# MixerHF.net
KiCad netlist of a schematic drawn in Altium Designer
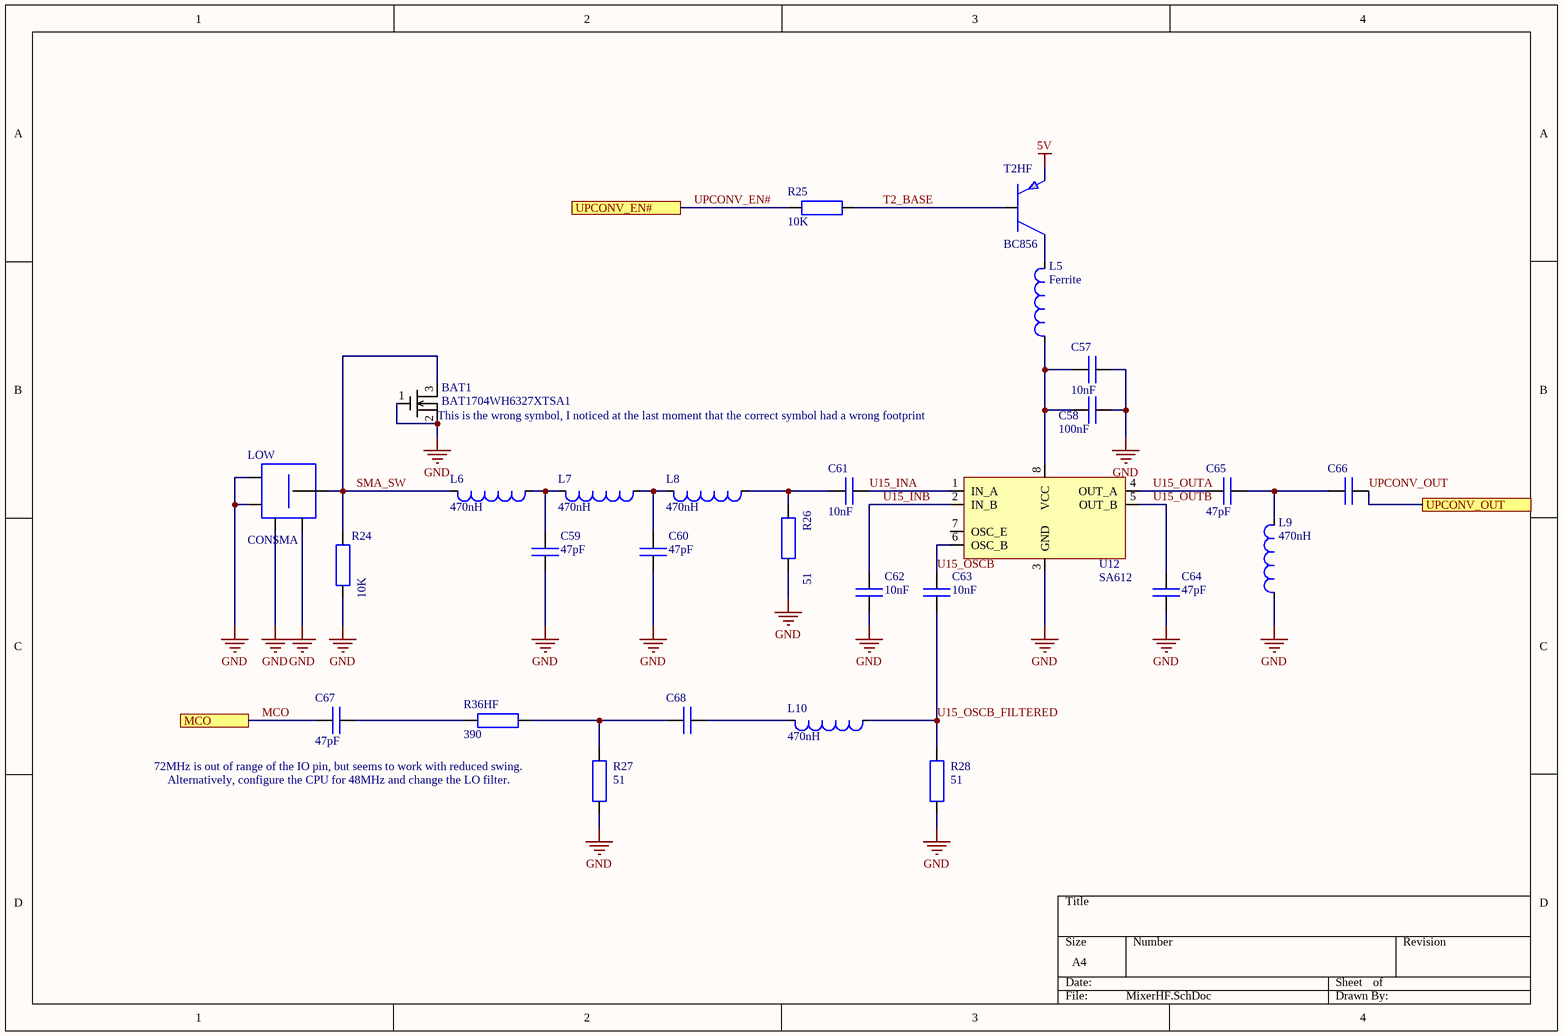
[diagram p0: MixerHF.SchDoc]

(export (version "E")
  (design (tool "Eeschema 10.0.6"))
  (components
    (comp (ref "BAT1")
      (value "BAT1704WH6327XTSA1")
      (footprint "SOT95P230X110-3N")
      (libsource (lib "library") (part "NX3008NBK"))
    )
    (comp (ref "C57")
      (value "10nF")
      (footprint "smd C0603_0.80")
      (description "smd capaciteit, verp.0603, 10nF")
      (fields (field (name "PART NUMBER") "CSMD603/10nF"))
      (libsource (lib "CDE_Library") (part "CSMD603/10nF"))
    )
    (comp (ref "C58")
      (value "100nF")
      (footprint "smd C0603_0.80")
      (description "smd capaciteit, verp.0603, 100nF")
      (fields (field (name "PART NUMBER") "CSMD603/100nF"))
      (libsource (lib "CDE_Library") (part "CSMD603/100nF"))
    )
    (comp (ref "C59")
      (value "47pF")
      (footprint "smd C0603_0.80")
      (description "smd capaciteit, verp.0603, 47pF")
      (fields (field (name "PART NUMBER") "CSMD603/47pF"))
      (libsource (lib "CDE_Library") (part "CSMD603/47pF"))
    )
    (comp (ref "C60")
      (value "47pF")
      (footprint "smd C0603_0.80")
      (description "smd capaciteit, verp.0603, 47pF")
      (fields (field (name "PART NUMBER") "CSMD603/47pF"))
      (libsource (lib "CDE_Library") (part "CSMD603/47pF"))
    )
    (comp (ref "C61")
      (value "10nF")
      (footprint "smd C0603_0.80")
      (description "smd capaciteit, verp.0603, 10nF")
      (fields (field (name "PART NUMBER") "CSMD603/10nF"))
      (libsource (lib "CDE_Library") (part "CSMD603/10nF"))
    )
    (comp (ref "C62")
      (value "10nF")
      (footprint "smd C0603_0.80")
      (description "smd capaciteit, verp.0603, 10nF")
      (fields (field (name "PART NUMBER") "CSMD603/10nF"))
      (libsource (lib "CDE_Library") (part "CSMD603/10nF"))
    )
    (comp (ref "C63")
      (value "10nF")
      (footprint "smd C0603_0.80")
      (description "smd capaciteit, verp.0603, 10nF")
      (fields (field (name "PART NUMBER") "CSMD603/10nF"))
      (libsource (lib "CDE_Library") (part "CSMD603/10nF"))
    )
    (comp (ref "C64")
      (value "47pF")
      (footprint "smd C0603_0.80")
      (description "smd capaciteit, verp.0603, 47pF")
      (fields (field (name "PART NUMBER") "CSMD603/47pF"))
      (libsource (lib "CDE_Library") (part "CSMD603/47pF"))
    )
    (comp (ref "C65")
      (value "47pF")
      (footprint "smd C0603_0.80")
      (description "smd capaciteit, verp.0603, 47pF")
      (fields (field (name "PART NUMBER") "CSMD603/47pF"))
      (libsource (lib "CDE_Library") (part "CSMD603/47pF"))
    )
    (comp (ref "C66")
      (value "~")
      (footprint "smd C0603_0.80")
      (description "smd capaciteit, verp.0603, 10pF")
      (fields (field (name "PART NUMBER") "CSMD603/10pF"))
      (libsource (lib "CDE_Library") (part "CSMD603/10pF"))
    )
    (comp (ref "C67")
      (value "47pF")
      (footprint "smd C0402")
      (description "smd capaciteit, verp.0402, 47pF")
      (fields (field (name "PART NUMBER") "CSMD402/47pF"))
      (libsource (lib "CDE_Library") (part "CSMD402/47pF"))
    )
    (comp (ref "C68")
      (value "~")
      (footprint "smd C0603_0.80")
      (description "smd capaciteit, verp.0603, 10pF")
      (fields (field (name "PART NUMBER") "CSMD603/10pF"))
      (libsource (lib "CDE_Library") (part "CSMD603/10pF"))
    )
    (comp (ref "L5")
      (value "Ferrite")
      (footprint "smd C0805")
      (description "Ferrite bead, 0805 package")
      (libsource (lib "CDE_Library") (part "Ferrite 0805"))
    )
    (comp (ref "L6")
      (value "470nH")
      (footprint "smd C0805")
      (description "smd spoel, verpakking 805, 470nH")
      (libsource (lib "CDE_Library") (part "SPL805/470nH"))
    )
    (comp (ref "L7")
      (value "470nH")
      (footprint "smd C0805")
      (description "smd spoel, verpakking 805, 470nH")
      (libsource (lib "CDE_Library") (part "SPL805/470nH"))
    )
    (comp (ref "L8")
      (value "470nH")
      (footprint "smd C0805")
      (description "smd spoel, verpakking 805, 470nH")
      (libsource (lib "CDE_Library") (part "SPL805/470nH"))
    )
    (comp (ref "L9")
      (value "470nH")
      (footprint "smd C0805")
      (description "smd spoel, verpakking 805, 470nH")
      (libsource (lib "CDE_Library") (part "SPL805/470nH"))
    )
    (comp (ref "L10")
      (value "470nH")
      (footprint "smd C0805")
      (description "smd spoel, verpakking 805, 470nH")
      (libsource (lib "CDE_Library") (part "SPL805/470nH"))
    )
    (comp (ref "LOW")
      (value "CONSMA")
      (footprint "con SMA (recht)")
      (description "SMA connector, rechtop")
      (fields (field (name "PART NUMBER") "CON SMA"))
      (libsource (lib "CDE_Library") (part "CON SMA"))
    )
    (comp (ref "R24")
      (value "10K")
      (footprint "smd C0603_0.45")
      (description "weerstand SMD603, 10K")
      (libsource (lib "CDE_Library") (part "10K/603"))
    )
    (comp (ref "R25")
      (value "10K")
      (footprint "smd C0603_0.45")
      (description "weerstand SMD603, 10K")
      (libsource (lib "CDE_Library") (part "10K/603"))
    )
    (comp (ref "R26")
      (value "51")
      (footprint "smd C0603_0.45")
      (description "weerstand SMD603, 51R")
      (libsource (lib "CDE_Library") (part "51R/603"))
    )
    (comp (ref "R27")
      (value "51")
      (footprint "smd C0603_0.45")
      (description "weerstand SMD603, 51R")
      (libsource (lib "CDE_Library") (part "51R/603"))
    )
    (comp (ref "R28")
      (value "51")
      (footprint "smd C0603_0.45")
      (description "weerstand SMD603, 51R")
      (libsource (lib "CDE_Library") (part "51R/603"))
    )
    (comp (ref "R36HF")
      (value "390")
      (footprint "smd C0603_0.45")
      (description "weerstand SMD603, 390R")
      (libsource (lib "CDE_Library") (part "390R/603"))
    )
    (comp (ref "T2HF")
      (value "BC856")
      (footprint "smd SOT-23")
      (description "PNP transistor, smd")
      (libsource (lib "CDE_Library") (part "BC856"))
    )
    (comp (ref "U12")
      (value "SA612")
      (footprint "SOIC127P600X175-8N")
      (libsource (lib "library") (part "SA612"))
    )
  )
  (nets
    (net (code "1") (name "/MCO") (class "Default") (node (ref "C67") (pin "2") (pintype "passive")))
    (net (code "2") (name "/SMA_SW") (class "Default")
      (node (ref "BAT1") (pin "3") (pinfunction "D_3") (pintype "passive"))
      (node (ref "L6") (pin "2") (pintype "passive"))
      (node (ref "LOW") (pin "1") (pintype "passive"))
      (node (ref "R24") (pin "2") (pintype "passive"))
    )
    (net (code "3") (name "/T2_BASE") (class "Default")
      (node (ref "R25") (pin "2") (pintype "passive"))
      (node (ref "T2HF") (pin "1") (pintype "passive"))
    )
    (net (code "4") (name "/U15_INA") (class "Default")
      (node (ref "C61") (pin "1") (pintype "passive"))
      (node (ref "U12") (pin "1") (pinfunction "IN_A_1") (pintype "passive"))
    )
    (net (code "5") (name "/U15_INB") (class "Default")
      (node (ref "C62") (pin "1") (pintype "passive"))
      (node (ref "U12") (pin "2") (pinfunction "IN_B_2") (pintype "passive"))
    )
    (net (code "6") (name "/U15_OSCB") (class "Default")
      (node (ref "C63") (pin "1") (pintype "passive"))
      (node (ref "U12") (pin "6") (pinfunction "OSC_B_6") (pintype "passive"))
    )
    (net (code "7") (name "/U15_OSCB_FILTERED") (class "Default")
      (node (ref "C63") (pin "2") (pintype "passive"))
      (node (ref "L10") (pin "1") (pintype "passive"))
      (node (ref "R28") (pin "1") (pintype "passive"))
    )
    (net (code "8") (name "/U15_OUTA") (class "Default")
      (node (ref "C65") (pin "1") (pintype "passive"))
      (node (ref "U12") (pin "4") (pinfunction "OUT_A_4") (pintype "passive"))
    )
    (net (code "9") (name "/U15_OUTB") (class "Default")
      (node (ref "C64") (pin "2") (pintype "passive"))
      (node (ref "U12") (pin "5") (pinfunction "OUT_B_5") (pintype "passive"))
    )
    (net (code "10") (name "/UPCONV_EN#") (class "Default") (node (ref "R25") (pin "1") (pintype "passive")))
    (net (code "11") (name "/UPCONV_OUT") (class "Default") (node (ref "C66") (pin "2") (pintype "passive")))
    (net (code "12") (name "5V") (class "Default") (node (ref "T2HF") (pin "2") (pintype "passive")))
    (net (code "13") (name "GND") (class "Default")
      (node (ref "BAT1") (pin "1") (pinfunction "G_1") (pintype "passive"))
      (node (ref "BAT1") (pin "2") (pinfunction "S_2") (pintype "passive"))
      (node (ref "C57") (pin "1") (pintype "passive"))
      (node (ref "C58") (pin "1") (pintype "passive"))
      (node (ref "C59") (pin "1") (pintype "passive"))
      (node (ref "C60") (pin "1") (pintype "passive"))
      (node (ref "C62") (pin "2") (pintype "passive"))
      (node (ref "C64") (pin "1") (pintype "passive"))
      (node (ref "L9") (pin "1") (pintype "passive"))
      (node (ref "LOW") (pin "2") (pintype "passive"))
      (node (ref "LOW") (pin "3") (pintype "passive"))
      (node (ref "LOW") (pin "4") (pintype "passive"))
      (node (ref "LOW") (pin "5") (pintype "passive"))
      (node (ref "R24") (pin "1") (pintype "passive"))
      (node (ref "R26") (pin "1") (pintype "passive"))
      (node (ref "R27") (pin "2") (pintype "passive"))
      (node (ref "R28") (pin "2") (pintype "passive"))
      (node (ref "U12") (pin "3") (pinfunction "GND_3") (pintype "passive"))
    )
    (net (code "14") (name "Net-(C59-Pad2)") (class "Default")
      (node (ref "C59") (pin "2") (pintype "passive"))
      (node (ref "L6") (pin "1") (pintype "passive"))
      (node (ref "L7") (pin "2") (pintype "passive"))
    )
    (net (code "15") (name "Net-(C60-Pad2)") (class "Default")
      (node (ref "C60") (pin "2") (pintype "passive"))
      (node (ref "L7") (pin "1") (pintype "passive"))
      (node (ref "L8") (pin "2") (pintype "passive"))
    )
    (net (code "16") (name "Net-(C61-Pad2)") (class "Default")
      (node (ref "C61") (pin "2") (pintype "passive"))
      (node (ref "L8") (pin "1") (pintype "passive"))
      (node (ref "R26") (pin "2") (pintype "passive"))
    )
    (net (code "17") (name "Net-(C65-Pad2)") (class "Default")
      (node (ref "C65") (pin "2") (pintype "passive"))
      (node (ref "C66") (pin "1") (pintype "passive"))
      (node (ref "L9") (pin "2") (pintype "passive"))
    )
    (net (code "18") (name "Net-(C67-Pad1)") (class "Default")
      (node (ref "C67") (pin "1") (pintype "passive"))
      (node (ref "R36HF") (pin "2") (pintype "passive"))
    )
    (net (code "19") (name "Net-(C68-Pad1)") (class "Default")
      (node (ref "C68") (pin "1") (pintype "passive"))
      (node (ref "L10") (pin "2") (pintype "passive"))
    )
    (net (code "20") (name "Net-(C68-Pad2)") (class "Default")
      (node (ref "C68") (pin "2") (pintype "passive"))
      (node (ref "R27") (pin "1") (pintype "passive"))
      (node (ref "R36HF") (pin "1") (pintype "passive"))
    )
    (net (code "21") (name "Net-(L5-Pad2)") (class "Default")
      (node (ref "L5") (pin "2") (pintype "passive"))
      (node (ref "T2HF") (pin "3") (pintype "passive"))
    )
    (net (code "22") (name "Net-(U12-VCC)") (class "Default")
      (node (ref "C57") (pin "2") (pintype "passive"))
      (node (ref "C58") (pin "2") (pintype "passive"))
      (node (ref "L5") (pin "1") (pintype "passive"))
      (node (ref "U12") (pin "8") (pinfunction "VCC_8") (pintype "passive"))
    )
    (net (code "23") (name "unconnected-(U12-OSC_E-Pad7)") (class "Default")
      (node (ref "U12") (pin "7") (pinfunction "OSC_E_7") (pintype "passive"))
    )
  )
)
